# TJMakes_IO_Expander.net
KiCad netlist of a schematic drawn in EasyEDA Pro
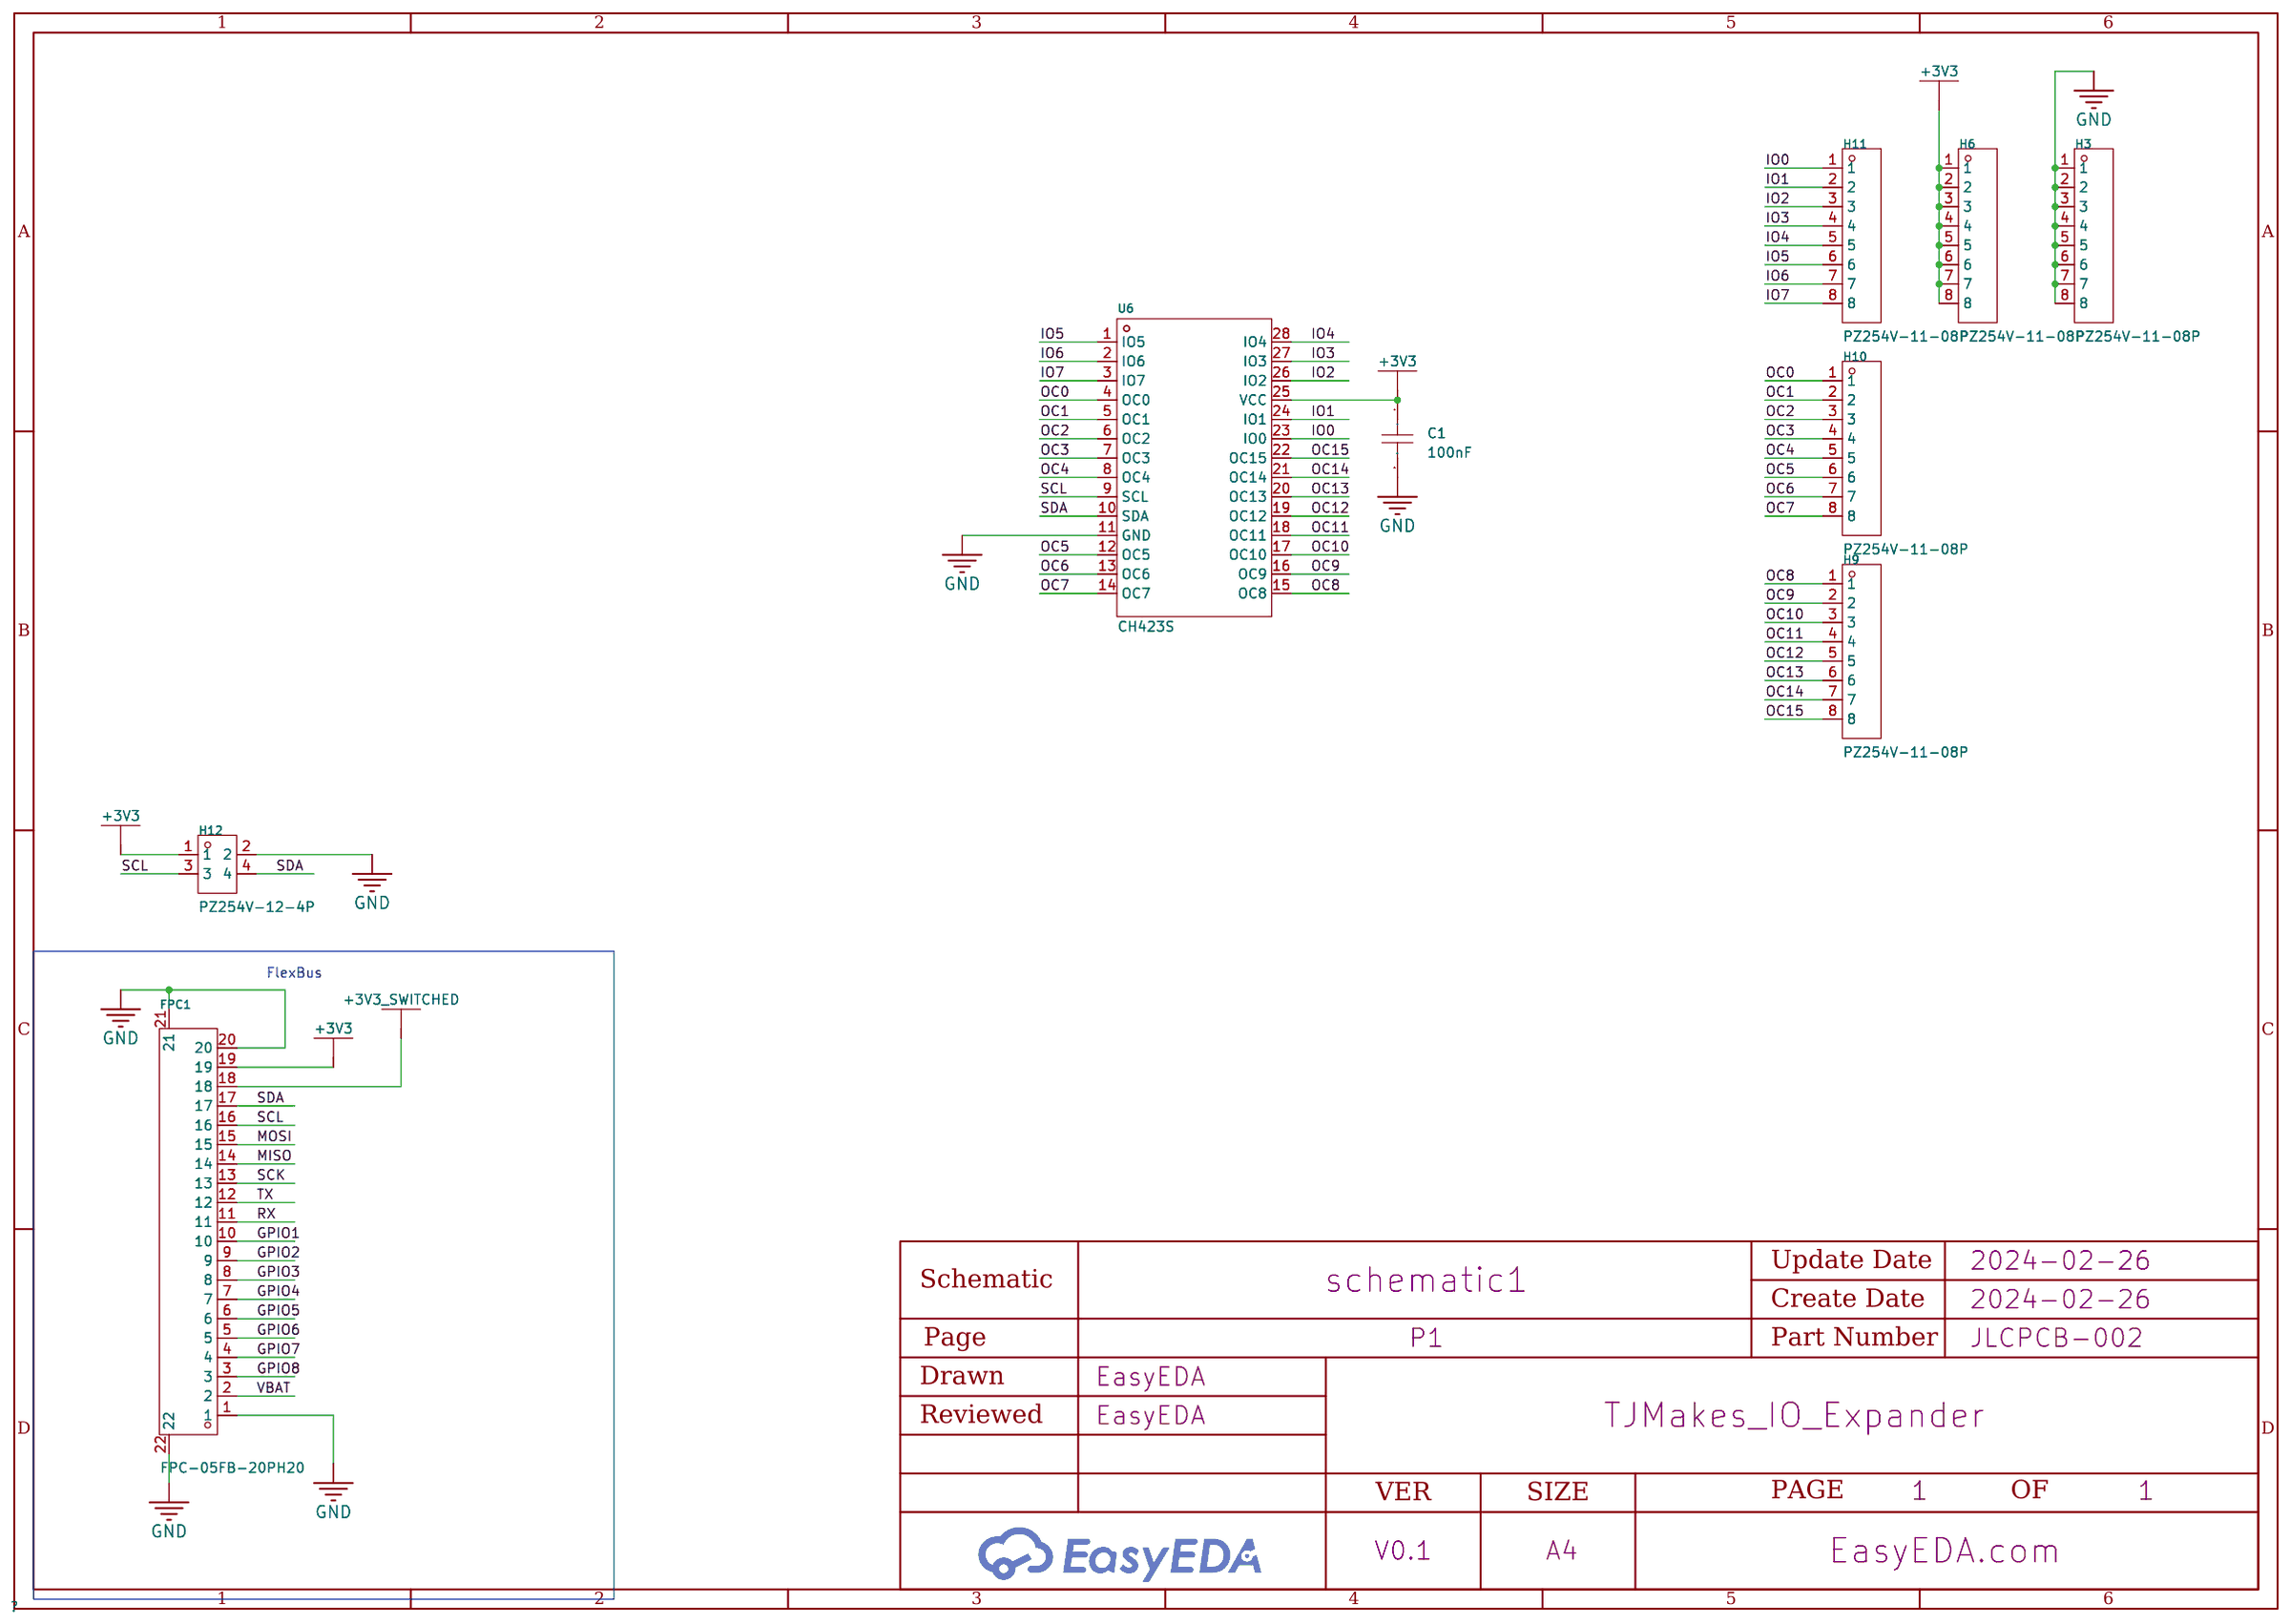
[diagram p0: schematic sheet]

(export (version "E")
  (design (tool "Eeschema 10.0.6"))
  (components
    (comp (ref "C1")
      (value "100nF")
      (footprint "easyedapro:C0603")
      (libsource (lib "easyedapro") (part "CAP"))
    )
    (comp (ref "FPC1")
      (value "FPC-05FB-20PH20")
      (footprint "easyedapro:FPC-SMD_20P-P0.50_FPC-05FB-20PH20")
      (fields (field (name "Manufacturer") "XUNPU(讯普)"))
      (libsource (lib "easyedapro") (part "FPC-05FB-20PH20"))
    )
    (comp (ref "H3")
      (value "PZ254V-11-08P")
      (footprint "easyedapro:HDR-TH_8P-P2.54-V-M")
      (fields (field (name "Manufacturer") "XFCN(兴飞)"))
      (libsource (lib "easyedapro") (part "PZ254V-11-08P"))
    )
    (comp (ref "H6")
      (value "PZ254V-11-08P")
      (footprint "easyedapro:HDR-TH_8P-P2.54-V-M")
      (fields (field (name "Manufacturer") "XFCN(兴飞)"))
      (libsource (lib "easyedapro") (part "PZ254V-11-08P"))
    )
    (comp (ref "H9")
      (value "PZ254V-11-08P")
      (footprint "easyedapro:HDR-TH_8P-P2.54-V-M")
      (fields (field (name "Manufacturer") "XFCN(兴飞)"))
      (libsource (lib "easyedapro") (part "PZ254V-11-08P"))
    )
    (comp (ref "H10")
      (value "PZ254V-11-08P")
      (footprint "easyedapro:HDR-TH_8P-P2.54-V-M")
      (fields (field (name "Manufacturer") "XFCN(兴飞)"))
      (libsource (lib "easyedapro") (part "PZ254V-11-08P"))
    )
    (comp (ref "H11")
      (value "PZ254V-11-08P")
      (footprint "easyedapro:HDR-TH_8P-P2.54-V-M")
      (fields (field (name "Manufacturer") "XFCN(兴飞)"))
      (libsource (lib "easyedapro") (part "PZ254V-11-08P"))
    )
    (comp (ref "H12")
      (value "PZ254V-12-4P")
      (footprint "easyedapro:HDR-TH_4P-P2.54-V-M-R2-C2-S2.54")
      (fields (field (name "Manufacturer") "XFCN(兴飞)"))
      (libsource (lib "easyedapro") (part "PZ254V-12-4P"))
    )
    (comp (ref "U6")
      (value "CH423S")
      (footprint "easyedapro:SOP-28_L17.9-W7.5-P1.27-LS10.3-BL")
      (fields (field (name "Manufacturer") "WCH(南京沁恒)"))
      (libsource (lib "easyedapro") (part "CH423S"))
    )
  )
  (nets
    (net (code "1") (name "+3V3") (class "Default")
      (node (ref "C1") (pin "1") (pinfunction "1_1") (pintype "input"))
      (node (ref "FPC1") (pin "19") (pinfunction "19_19") (pintype "input"))
      (node (ref "H12") (pin "1") (pinfunction "1_1") (pintype "input"))
      (node (ref "H6") (pin "1") (pinfunction "1_1") (pintype "input"))
      (node (ref "H6") (pin "2") (pinfunction "2_2") (pintype "input"))
      (node (ref "H6") (pin "3") (pinfunction "3_3") (pintype "input"))
      (node (ref "H6") (pin "4") (pinfunction "4_4") (pintype "input"))
      (node (ref "H6") (pin "5") (pinfunction "5_5") (pintype "input"))
      (node (ref "H6") (pin "6") (pinfunction "6_6") (pintype "input"))
      (node (ref "H6") (pin "7") (pinfunction "7_7") (pintype "input"))
      (node (ref "H6") (pin "8") (pinfunction "8_8") (pintype "input"))
      (node (ref "U6") (pin "25") (pinfunction "VCC_25") (pintype "input"))
    )
    (net (code "2") (name "+3V3_SWITCHED") (class "Default")
      (node (ref "FPC1") (pin "18") (pinfunction "18_18") (pintype "input"))
    )
    (net (code "3") (name "/GPIO1") (class "Default")
      (node (ref "FPC1") (pin "10") (pinfunction "10_10") (pintype "input"))
    )
    (net (code "4") (name "/GPIO2") (class "Default")
      (node (ref "FPC1") (pin "9") (pinfunction "9_9") (pintype "input"))
    )
    (net (code "5") (name "/GPIO3") (class "Default")
      (node (ref "FPC1") (pin "8") (pinfunction "8_8") (pintype "input"))
    )
    (net (code "6") (name "/GPIO4") (class "Default")
      (node (ref "FPC1") (pin "7") (pinfunction "7_7") (pintype "input"))
    )
    (net (code "7") (name "/GPIO5") (class "Default")
      (node (ref "FPC1") (pin "6") (pinfunction "6_6") (pintype "input"))
    )
    (net (code "8") (name "/GPIO6") (class "Default")
      (node (ref "FPC1") (pin "5") (pinfunction "5_5") (pintype "input"))
    )
    (net (code "9") (name "/GPIO7") (class "Default")
      (node (ref "FPC1") (pin "4") (pinfunction "4_4") (pintype "input"))
    )
    (net (code "10") (name "/GPIO8") (class "Default")
      (node (ref "FPC1") (pin "3") (pinfunction "3_3") (pintype "input"))
    )
    (net (code "11") (name "/IO0") (class "Default")
      (node (ref "H11") (pin "1") (pinfunction "1_1") (pintype "input"))
      (node (ref "U6") (pin "23") (pinfunction "IO0_23") (pintype "input"))
    )
    (net (code "12") (name "/IO1") (class "Default")
      (node (ref "H11") (pin "2") (pinfunction "2_2") (pintype "input"))
      (node (ref "U6") (pin "24") (pinfunction "IO1_24") (pintype "input"))
    )
    (net (code "13") (name "/IO2") (class "Default")
      (node (ref "H11") (pin "3") (pinfunction "3_3") (pintype "input"))
      (node (ref "U6") (pin "26") (pinfunction "IO2_26") (pintype "input"))
    )
    (net (code "14") (name "/IO3") (class "Default")
      (node (ref "H11") (pin "4") (pinfunction "4_4") (pintype "input"))
      (node (ref "U6") (pin "27") (pinfunction "IO3_27") (pintype "input"))
    )
    (net (code "15") (name "/IO4") (class "Default")
      (node (ref "H11") (pin "5") (pinfunction "5_5") (pintype "input"))
      (node (ref "U6") (pin "28") (pinfunction "IO4_28") (pintype "input"))
    )
    (net (code "16") (name "/IO5") (class "Default")
      (node (ref "H11") (pin "6") (pinfunction "6_6") (pintype "input"))
      (node (ref "U6") (pin "1") (pinfunction "IO5_1") (pintype "input"))
    )
    (net (code "17") (name "/IO6") (class "Default")
      (node (ref "H11") (pin "7") (pinfunction "7_7") (pintype "input"))
      (node (ref "U6") (pin "2") (pinfunction "IO6_2") (pintype "input"))
    )
    (net (code "18") (name "/IO7") (class "Default")
      (node (ref "H11") (pin "8") (pinfunction "8_8") (pintype "input"))
      (node (ref "U6") (pin "3") (pinfunction "IO7_3") (pintype "input"))
    )
    (net (code "19") (name "/MISO") (class "Default")
      (node (ref "FPC1") (pin "14") (pinfunction "14_14") (pintype "input"))
    )
    (net (code "20") (name "/MOSI") (class "Default")
      (node (ref "FPC1") (pin "15") (pinfunction "15_15") (pintype "input"))
    )
    (net (code "21") (name "/OC0") (class "Default")
      (node (ref "H10") (pin "1") (pinfunction "1_1") (pintype "input"))
      (node (ref "U6") (pin "4") (pinfunction "OC0_4") (pintype "input"))
    )
    (net (code "22") (name "/OC1") (class "Default")
      (node (ref "H10") (pin "2") (pinfunction "2_2") (pintype "input"))
      (node (ref "U6") (pin "5") (pinfunction "OC1_5") (pintype "input"))
    )
    (net (code "23") (name "/OC2") (class "Default")
      (node (ref "H10") (pin "3") (pinfunction "3_3") (pintype "input"))
      (node (ref "U6") (pin "6") (pinfunction "OC2_6") (pintype "input"))
    )
    (net (code "24") (name "/OC3") (class "Default")
      (node (ref "H10") (pin "4") (pinfunction "4_4") (pintype "input"))
      (node (ref "U6") (pin "7") (pinfunction "OC3_7") (pintype "input"))
    )
    (net (code "25") (name "/OC4") (class "Default")
      (node (ref "H10") (pin "5") (pinfunction "5_5") (pintype "input"))
      (node (ref "U6") (pin "8") (pinfunction "OC4_8") (pintype "input"))
    )
    (net (code "26") (name "/OC5") (class "Default")
      (node (ref "H10") (pin "6") (pinfunction "6_6") (pintype "input"))
      (node (ref "U6") (pin "12") (pinfunction "OC5_12") (pintype "input"))
    )
    (net (code "27") (name "/OC6") (class "Default")
      (node (ref "H10") (pin "7") (pinfunction "7_7") (pintype "input"))
      (node (ref "U6") (pin "13") (pinfunction "OC6_13") (pintype "input"))
    )
    (net (code "28") (name "/OC7") (class "Default")
      (node (ref "H10") (pin "8") (pinfunction "8_8") (pintype "input"))
      (node (ref "U6") (pin "14") (pinfunction "OC7_14") (pintype "input"))
    )
    (net (code "29") (name "/OC8") (class "Default")
      (node (ref "H9") (pin "1") (pinfunction "1_1") (pintype "input"))
      (node (ref "U6") (pin "15") (pinfunction "OC8_15") (pintype "input"))
    )
    (net (code "30") (name "/OC9") (class "Default")
      (node (ref "H9") (pin "2") (pinfunction "2_2") (pintype "input"))
      (node (ref "U6") (pin "16") (pinfunction "OC9_16") (pintype "input"))
    )
    (net (code "31") (name "/OC10") (class "Default")
      (node (ref "H9") (pin "3") (pinfunction "3_3") (pintype "input"))
      (node (ref "U6") (pin "17") (pinfunction "OC10_17") (pintype "input"))
    )
    (net (code "32") (name "/OC11") (class "Default")
      (node (ref "H9") (pin "4") (pinfunction "4_4") (pintype "input"))
      (node (ref "U6") (pin "18") (pinfunction "OC11_18") (pintype "input"))
    )
    (net (code "33") (name "/OC12") (class "Default")
      (node (ref "H9") (pin "5") (pinfunction "5_5") (pintype "input"))
      (node (ref "U6") (pin "19") (pinfunction "OC12_19") (pintype "input"))
    )
    (net (code "34") (name "/OC13") (class "Default")
      (node (ref "H9") (pin "6") (pinfunction "6_6") (pintype "input"))
      (node (ref "U6") (pin "20") (pinfunction "OC13_20") (pintype "input"))
    )
    (net (code "35") (name "/OC14") (class "Default")
      (node (ref "H9") (pin "7") (pinfunction "7_7") (pintype "input"))
      (node (ref "U6") (pin "21") (pinfunction "OC14_21") (pintype "input"))
    )
    (net (code "36") (name "/OC15") (class "Default")
      (node (ref "H9") (pin "8") (pinfunction "8_8") (pintype "input"))
      (node (ref "U6") (pin "22") (pinfunction "OC15_22") (pintype "input"))
    )
    (net (code "37") (name "/RX") (class "Default")
      (node (ref "FPC1") (pin "11") (pinfunction "11_11") (pintype "input"))
    )
    (net (code "38") (name "/SCK") (class "Default")
      (node (ref "FPC1") (pin "13") (pinfunction "13_13") (pintype "input"))
    )
    (net (code "39") (name "/SCL") (class "Default")
      (node (ref "FPC1") (pin "16") (pinfunction "16_16") (pintype "input"))
      (node (ref "H12") (pin "3") (pinfunction "3_3") (pintype "input"))
      (node (ref "U6") (pin "9") (pinfunction "SCL_9") (pintype "input"))
    )
    (net (code "40") (name "/SDA") (class "Default")
      (node (ref "FPC1") (pin "17") (pinfunction "17_17") (pintype "input"))
      (node (ref "H12") (pin "4") (pinfunction "4_4") (pintype "input"))
      (node (ref "U6") (pin "10") (pinfunction "SDA_10") (pintype "input"))
    )
    (net (code "41") (name "/TX") (class "Default")
      (node (ref "FPC1") (pin "12") (pinfunction "12_12") (pintype "input"))
    )
    (net (code "42") (name "/VBAT") (class "Default")
      (node (ref "FPC1") (pin "2") (pinfunction "2_2") (pintype "input"))
    )
    (net (code "43") (name "GND") (class "Default")
      (node (ref "C1") (pin "2") (pinfunction "2_2") (pintype "input"))
      (node (ref "FPC1") (pin "1") (pinfunction "1_1") (pintype "input"))
      (node (ref "FPC1") (pin "20") (pinfunction "20_20") (pintype "input"))
      (node (ref "FPC1") (pin "21") (pinfunction "21_21") (pintype "input"))
      (node (ref "FPC1") (pin "22") (pinfunction "22_22") (pintype "input"))
      (node (ref "H12") (pin "2") (pinfunction "2_2") (pintype "input"))
      (node (ref "H3") (pin "1") (pinfunction "1_1") (pintype "input"))
      (node (ref "H3") (pin "2") (pinfunction "2_2") (pintype "input"))
      (node (ref "H3") (pin "3") (pinfunction "3_3") (pintype "input"))
      (node (ref "H3") (pin "4") (pinfunction "4_4") (pintype "input"))
      (node (ref "H3") (pin "5") (pinfunction "5_5") (pintype "input"))
      (node (ref "H3") (pin "6") (pinfunction "6_6") (pintype "input"))
      (node (ref "H3") (pin "7") (pinfunction "7_7") (pintype "input"))
      (node (ref "H3") (pin "8") (pinfunction "8_8") (pintype "input"))
      (node (ref "U6") (pin "11") (pinfunction "GND_11") (pintype "input"))
    )
  )
)
